# simple-transmitter-2n918.net
KiCad netlist of a schematic drawn in EAGLE
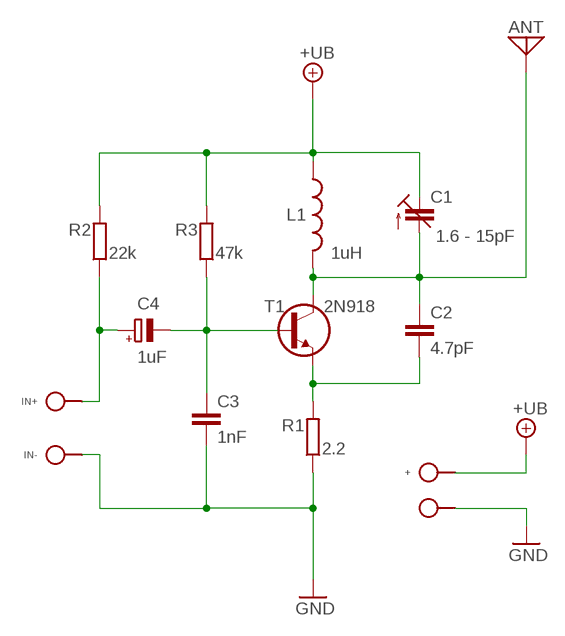
[diagram p0: schematic, sheet 1]

(export (version "E")
  (design (tool "Eeschema 10.0.6"))
  (components
    (comp (ref "+")
      (value "SPAD")
      (footprint "eagle-import:SPAD")
      (libsource (lib "eagle-import") (part "SPAD"))
    )
    (comp (ref "ANT")
      (value "ANT")
      (footprint "eagle-import:SPAD")
      (libsource (lib "eagle-import") (part "ANT"))
    )
    (comp (ref "C1")
      (value "1.6 - 15pF")
      (footprint "eagle-import:TRIM-2222-808")
      (libsource (lib "eagle-import") (part "C-TR-PH201272222-808-2PINB"))
    )
    (comp (ref "C2")
      (value "4.7pF")
      (footprint "eagle-import:C025-020X036")
      (libsource (lib "eagle-import") (part "C025-020X036"))
    )
    (comp (ref "C3")
      (value "1nF")
      (footprint "eagle-import:C025-020X036")
      (libsource (lib "eagle-import") (part "C025-020X036"))
    )
    (comp (ref "C4")
      (value "1uF")
      (footprint "eagle-import:E2,5-3")
      (libsource (lib "eagle-import") (part "CPOLE2,5-3"))
    )
    (comp (ref "IN+")
      (value "SPAD")
      (footprint "eagle-import:SPAD")
      (libsource (lib "eagle-import") (part "SPAD"))
    )
    (comp (ref "IN-")
      (value "SPAD")
      (footprint "eagle-import:SPAD")
      (libsource (lib "eagle-import") (part "SPAD"))
    )
    (comp (ref "L1")
      (value "1uH")
      (footprint "eagle-import:L-04_7")
      (libsource (lib "eagle-import") (part "L04/7"))
    )
    (comp (ref "R1")
      (value "2.2")
      (footprint "eagle-import:0202V")
      (libsource (lib "eagle-import") (part "R0202V"))
    )
    (comp (ref "R2")
      (value "22k")
      (footprint "eagle-import:0202_5")
      (libsource (lib "eagle-import") (part "R0202/5"))
    )
    (comp (ref "R3")
      (value "47k")
      (footprint "eagle-import:0202_5")
      (libsource (lib "eagle-import") (part "R0202/5"))
    )
    (comp (ref "T1")
      (value "2N918")
      (footprint "eagle-import:TO-72")
      (libsource (lib "eagle-import") (part "2N918TO-72-CE"))
    )
    (comp (ref "̶̶")
      (value "SPAD")
      (footprint "eagle-import:SPAD")
      (libsource (lib "eagle-import") (part "SPAD"))
    )
  )
  (nets
    (net (code "1") (name "+UB") (class "Default")
      (node (ref "+") (pin "1") (pinfunction "P$1_1") (pintype "bidirectional"))
      (node (ref "C1") (pin "3") (pinfunction "A_3") (pintype "passive"))
      (node (ref "L1") (pin "1") (pinfunction "1_1") (pintype "passive"))
      (node (ref "R2") (pin "2") (pinfunction "2_2") (pintype "passive"))
      (node (ref "R3") (pin "2") (pinfunction "2_2") (pintype "passive"))
    )
    (net (code "2") (name "GND") (class "Default")
      (node (ref "C3") (pin "2") (pinfunction "2_2") (pintype "passive"))
      (node (ref "IN-") (pin "1") (pinfunction "P$1_1") (pintype "bidirectional"))
      (node (ref "R1") (pin "1") (pinfunction "1_1") (pintype "passive"))
      (node (ref "̶̶") (pin "1") (pinfunction "P$1_1") (pintype "bidirectional"))
    )
    (net (code "3") (name "Net-(C1-E)") (class "Default")
      (node (ref "ANT") (pin "1") (pinfunction "1_1") (pintype "output"))
      (node (ref "C1") (pin "2") (pinfunction "E_2") (pintype "passive"))
      (node (ref "C2") (pin "1") (pinfunction "1_1") (pintype "passive"))
      (node (ref "L1") (pin "2") (pinfunction "2_2") (pintype "passive"))
      (node (ref "T1") (pin "3") (pinfunction "C_3") (pintype "passive"))
    )
    (net (code "4") (name "Net-(C2-Pad2)") (class "Default")
      (node (ref "C2") (pin "2") (pinfunction "2_2") (pintype "passive"))
      (node (ref "R1") (pin "2") (pinfunction "2_2") (pintype "passive"))
      (node (ref "T1") (pin "1") (pinfunction "E_1") (pintype "passive"))
      (node (ref "T1") (pin "4") (pinfunction "E_4") (pintype "passive"))
    )
    (net (code "5") (name "Net-(IN+-P$1)") (class "Default")
      (node (ref "C4") (pin "+") (pinfunction "+_+") (pintype "passive"))
      (node (ref "IN+") (pin "1") (pinfunction "P$1_1") (pintype "bidirectional"))
      (node (ref "R2") (pin "1") (pinfunction "1_1") (pintype "passive"))
    )
    (net (code "6") (name "Net-(T1-B)") (class "Default")
      (node (ref "C3") (pin "1") (pinfunction "1_1") (pintype "passive"))
      (node (ref "C4") (pin "-") (pinfunction "-_-") (pintype "passive"))
      (node (ref "R3") (pin "1") (pinfunction "1_1") (pintype "passive"))
      (node (ref "T1") (pin "2") (pinfunction "B_2") (pintype "passive"))
    )
  )
)
